# 2025-06-28.net
KiCad netlist of a schematic drawn in EasyEDA Pro
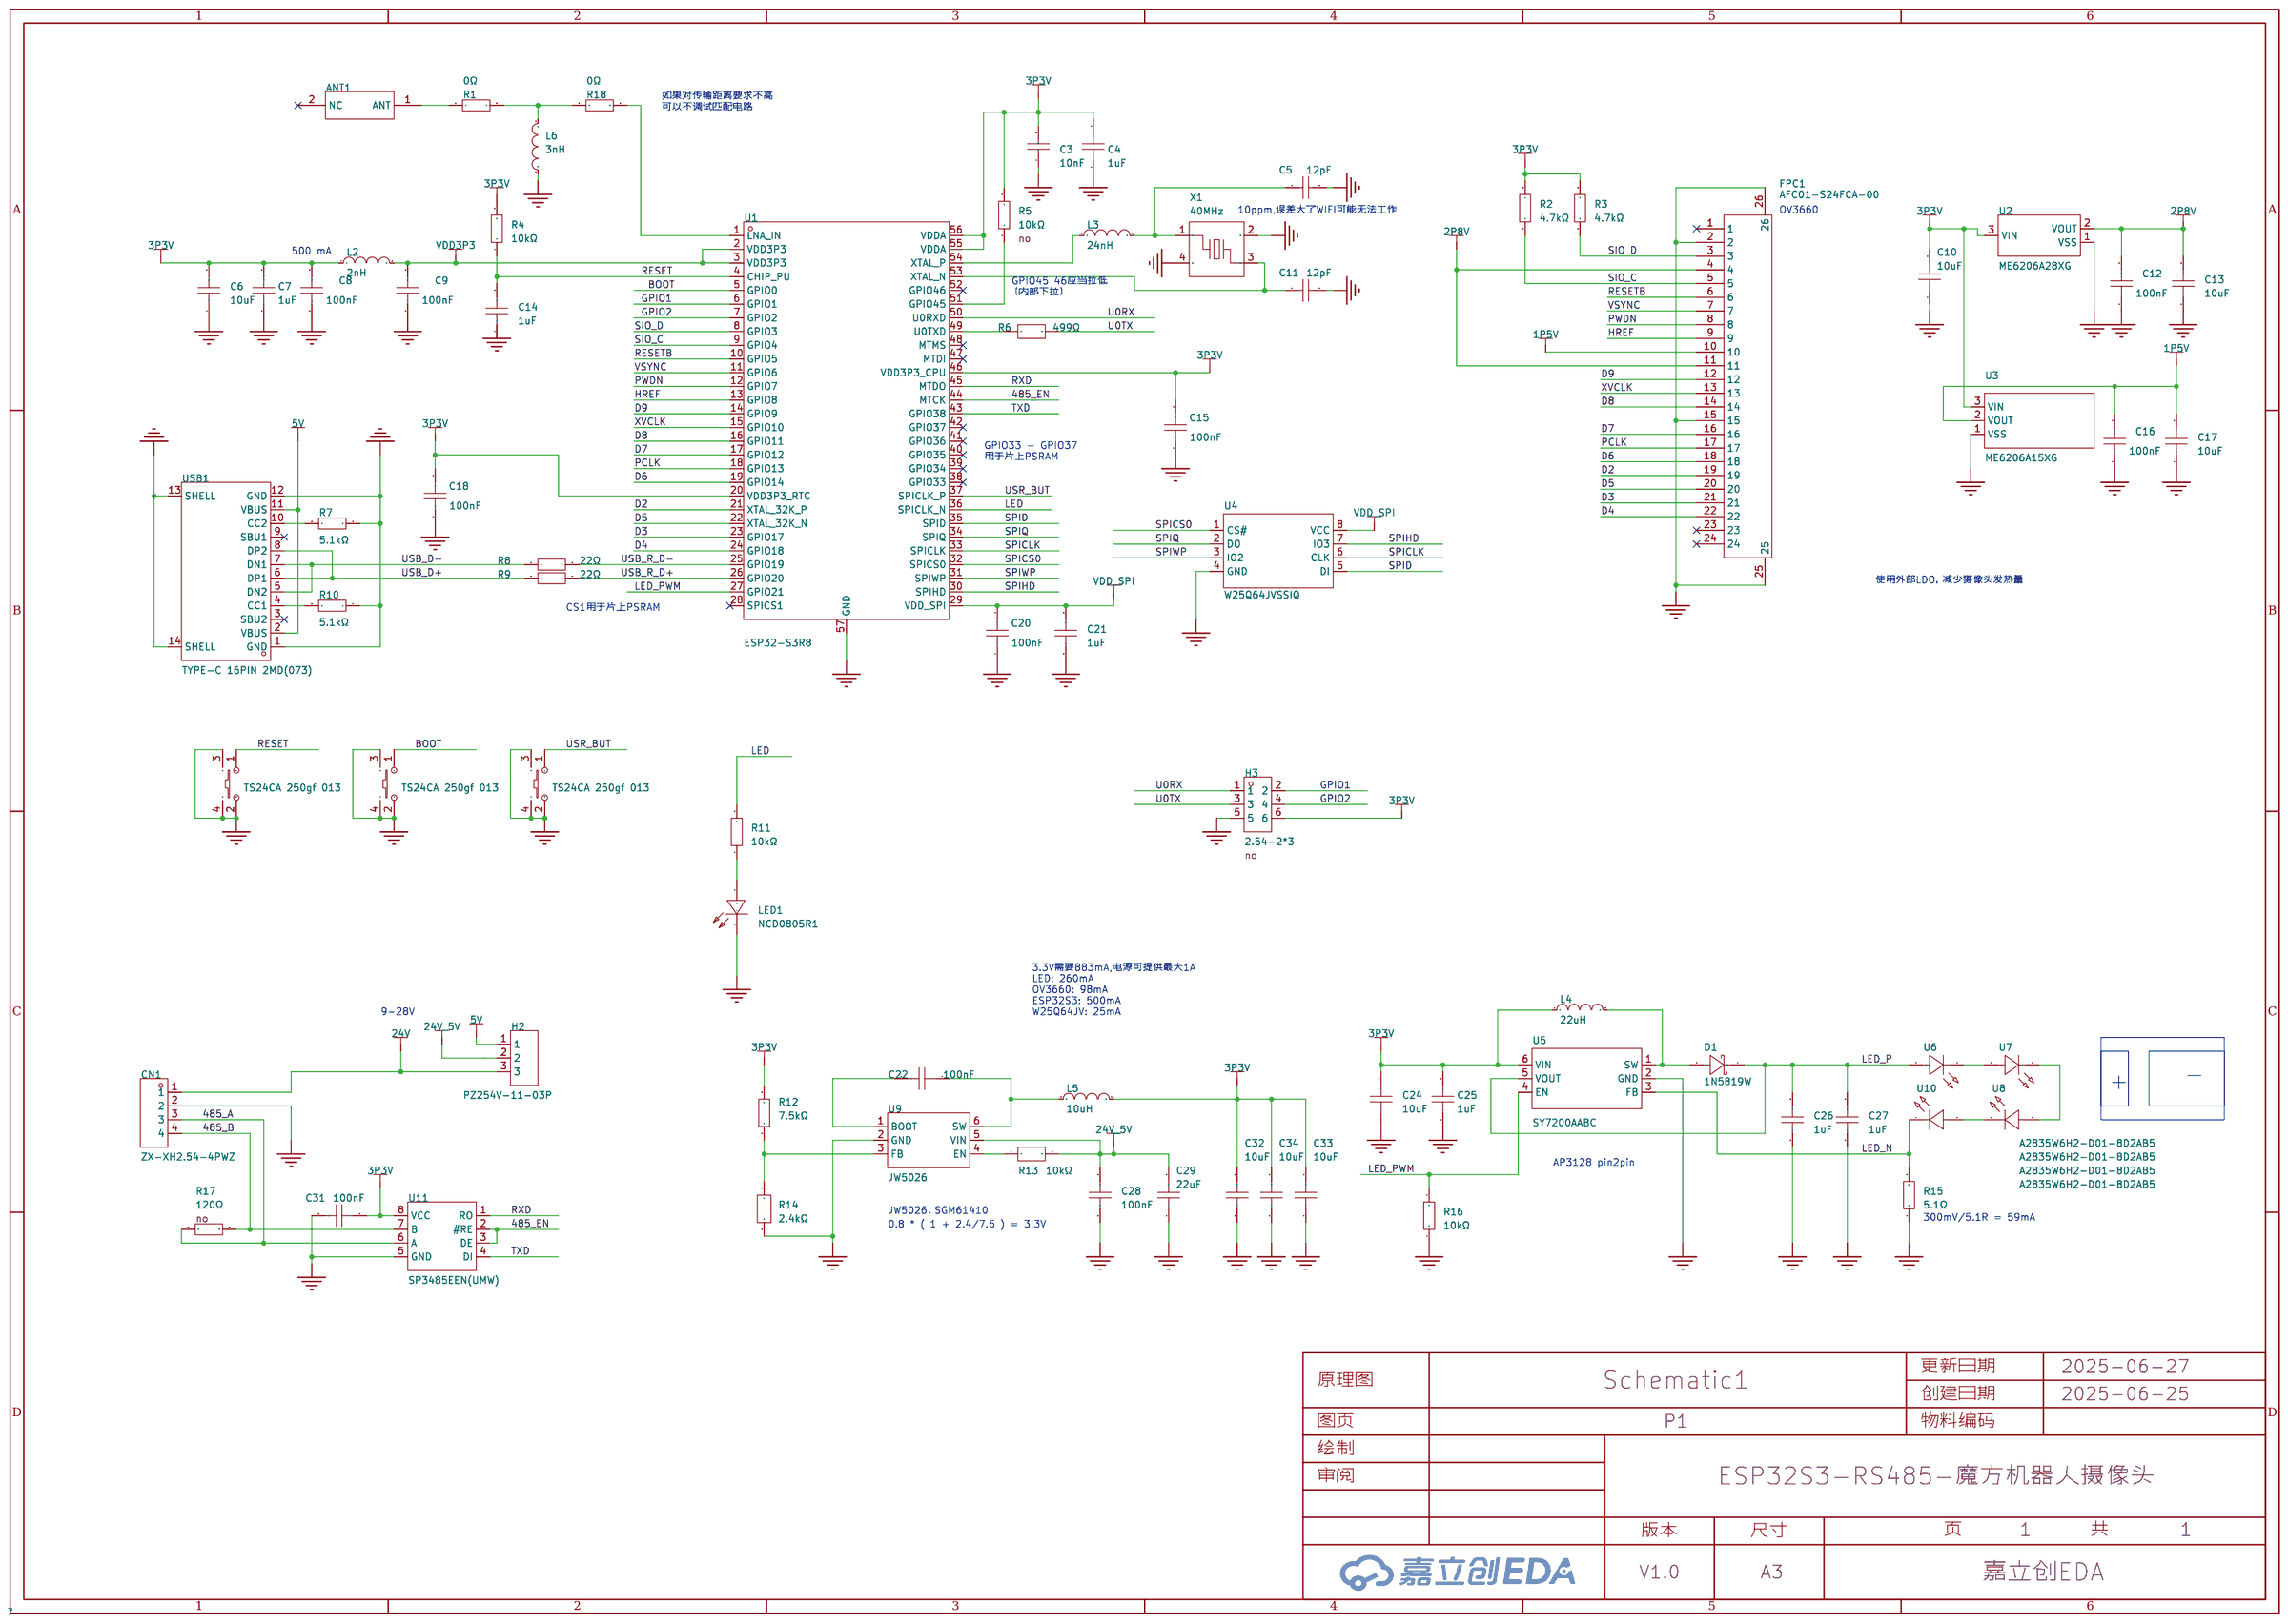
[diagram p0: schematic sheet]

(export (version "E")
  (design (tool "Eeschema 10.0.6"))
  (components
    (comp (ref "ANT1")
      (value "~")
      (footprint "easyedapro:CA-C03")
      (libsource (lib "easyedapro") (part "CA-C03"))
    )
    (comp (ref "C3")
      (value "10nF")
      (footprint "easyedapro:C0603")
      (description "容值:10nF;精度:±10%;额定电压:50V;温度系数:X7R;")
      (fields (field (name "Manufacturer Part") "0603B103K500NT") (field (name "Manufacturer") "FH(风华)"))
      (libsource (lib "easyedapro") (part "0603B103K500NT"))
    )
    (comp (ref "C4")
      (value "1uF")
      (footprint "easyedapro:C0603")
      (description "容值:1uF;精度:±10%;额定电压:50V;材质(温度系数):X5R;")
      (fields
        (field (name "Manufacturer Part") "CL10A105KB8NNNC")
        (field (name "Manufacturer") "SAMSUNG(三星)")
      )
      (libsource (lib "easyedapro") (part "CL10A105KB8NNNC"))
    )
    (comp (ref "C5")
      (value "12pF")
      (footprint "easyedapro:C0603")
      (description "容值:12pF;精度:±5%;额定电压:50V;材质(温度系数):C0G;")
      (fields
        (field (name "Manufacturer Part") "CL10C120JB8NNNC")
        (field (name "Manufacturer") "SAMSUNG(三星)")
      )
      (libsource (lib "easyedapro") (part "CL10C120JB8NNNC"))
    )
    (comp (ref "C6")
      (value "10uF")
      (footprint "easyedapro:C0603")
      (description "容值:10uF;精度:±10%;额定电压:10V;材质(温度系数):X5R;")
      (fields
        (field (name "Manufacturer Part") "CL10A106KP8NNNC")
        (field (name "Manufacturer") "SAMSUNG(三星)")
      )
      (libsource (lib "easyedapro") (part "CL10A106KP8NNNC"))
    )
    (comp (ref "C7")
      (value "1uF")
      (footprint "easyedapro:C0603")
      (description "容值:1uF;精度:±10%;额定电压:50V;材质(温度系数):X5R;")
      (fields
        (field (name "Manufacturer Part") "CL10A105KB8NNNC")
        (field (name "Manufacturer") "SAMSUNG(三星)")
      )
      (libsource (lib "easyedapro") (part "CL10A105KB8NNNC"))
    )
    (comp (ref "C8")
      (value "100nF")
      (footprint "easyedapro:C0603")
      (description "容值:100nF;精度:±10%;额定电压:50V;材质(温度系数):X7R;")
      (fields
        (field (name "Manufacturer Part") "CC0603KRX7R9BB104")
        (field (name "Manufacturer") "YAGEO(国巨)")
      )
      (libsource (lib "easyedapro") (part "CC0603KRX7R9BB104"))
    )
    (comp (ref "C9")
      (value "100nF")
      (footprint "easyedapro:C0603")
      (description "容值:100nF;精度:±10%;额定电压:50V;材质(温度系数):X7R;")
      (fields
        (field (name "Manufacturer Part") "CC0603KRX7R9BB104")
        (field (name "Manufacturer") "YAGEO(国巨)")
      )
      (libsource (lib "easyedapro") (part "CC0603KRX7R9BB104"))
    )
    (comp (ref "C10")
      (value "10uF")
      (footprint "easyedapro:C0603")
      (description "容值:10uF;精度:±10%;额定电压:10V;材质(温度系数):X5R;")
      (fields
        (field (name "Manufacturer Part") "CL10A106KP8NNNC")
        (field (name "Manufacturer") "SAMSUNG(三星)")
      )
      (libsource (lib "easyedapro") (part "CL10A106KP8NNNC"))
    )
    (comp (ref "C11")
      (value "12pF")
      (footprint "easyedapro:C0603")
      (description "容值:12pF;精度:±5%;额定电压:50V;材质(温度系数):C0G;")
      (fields
        (field (name "Manufacturer Part") "CL10C120JB8NNNC")
        (field (name "Manufacturer") "SAMSUNG(三星)")
      )
      (libsource (lib "easyedapro") (part "CL10C120JB8NNNC"))
    )
    (comp (ref "C12")
      (value "100nF")
      (footprint "easyedapro:C0603")
      (description "容值:100nF;精度:±10%;额定电压:50V;材质(温度系数):X7R;")
      (fields
        (field (name "Manufacturer Part") "CC0603KRX7R9BB104")
        (field (name "Manufacturer") "YAGEO(国巨)")
      )
      (libsource (lib "easyedapro") (part "CC0603KRX7R9BB104"))
    )
    (comp (ref "C13")
      (value "10uF")
      (footprint "easyedapro:C0603")
      (description "容值:10uF;精度:±10%;额定电压:10V;材质(温度系数):X5R;")
      (fields
        (field (name "Manufacturer Part") "CL10A106KP8NNNC")
        (field (name "Manufacturer") "SAMSUNG(三星)")
      )
      (libsource (lib "easyedapro") (part "CL10A106KP8NNNC"))
    )
    (comp (ref "C14")
      (value "1uF")
      (footprint "easyedapro:C0603")
      (description "容值:1uF;精度:±10%;额定电压:50V;材质(温度系数):X5R;")
      (fields
        (field (name "Manufacturer Part") "CL10A105KB8NNNC")
        (field (name "Manufacturer") "SAMSUNG(三星)")
      )
      (libsource (lib "easyedapro") (part "CL10A105KB8NNNC"))
    )
    (comp (ref "C15")
      (value "100nF")
      (footprint "easyedapro:C0603")
      (description "容值:100nF;精度:±10%;额定电压:50V;材质(温度系数):X7R;")
      (fields
        (field (name "Manufacturer Part") "CC0603KRX7R9BB104")
        (field (name "Manufacturer") "YAGEO(国巨)")
      )
      (libsource (lib "easyedapro") (part "CC0603KRX7R9BB104"))
    )
    (comp (ref "C16")
      (value "100nF")
      (footprint "easyedapro:C0603")
      (description "容值:100nF;精度:±10%;额定电压:50V;材质(温度系数):X7R;")
      (fields
        (field (name "Manufacturer Part") "CC0603KRX7R9BB104")
        (field (name "Manufacturer") "YAGEO(国巨)")
      )
      (libsource (lib "easyedapro") (part "CC0603KRX7R9BB104"))
    )
    (comp (ref "C17")
      (value "10uF")
      (footprint "easyedapro:C0603")
      (description "容值:10uF;精度:±10%;额定电压:10V;材质(温度系数):X5R;")
      (fields
        (field (name "Manufacturer Part") "CL10A106KP8NNNC")
        (field (name "Manufacturer") "SAMSUNG(三星)")
      )
      (libsource (lib "easyedapro") (part "CL10A106KP8NNNC"))
    )
    (comp (ref "C18")
      (value "100nF")
      (footprint "easyedapro:C0603")
      (description "容值:100nF;精度:±10%;额定电压:50V;材质(温度系数):X7R;")
      (fields
        (field (name "Manufacturer Part") "CC0603KRX7R9BB104")
        (field (name "Manufacturer") "YAGEO(国巨)")
      )
      (libsource (lib "easyedapro") (part "CC0603KRX7R9BB104"))
    )
    (comp (ref "C20")
      (value "100nF")
      (footprint "easyedapro:C0603")
      (description "容值:100nF;精度:±10%;额定电压:50V;材质(温度系数):X7R;")
      (fields
        (field (name "Manufacturer Part") "CC0603KRX7R9BB104")
        (field (name "Manufacturer") "YAGEO(国巨)")
      )
      (libsource (lib "easyedapro") (part "CC0603KRX7R9BB104"))
    )
    (comp (ref "C21")
      (value "1uF")
      (footprint "easyedapro:C0603")
      (description "容值:1uF;精度:±10%;额定电压:50V;材质(温度系数):X5R;")
      (fields
        (field (name "Manufacturer Part") "CL10A105KB8NNNC")
        (field (name "Manufacturer") "SAMSUNG(三星)")
      )
      (libsource (lib "easyedapro") (part "CL10A105KB8NNNC"))
    )
    (comp (ref "C22")
      (value "100nF")
      (footprint "easyedapro:C0603")
      (description "容值:100nF;精度:±10%;额定电压:50V;材质(温度系数):X7R;")
      (fields
        (field (name "Manufacturer Part") "CC0603KRX7R9BB104")
        (field (name "Manufacturer") "YAGEO(国巨)")
      )
      (libsource (lib "easyedapro") (part "CC0603KRX7R9BB104"))
    )
    (comp (ref "C24")
      (value "10uF")
      (footprint "easyedapro:C0603")
      (description "容值:10uF;精度:±10%;额定电压:10V;材质(温度系数):X5R;")
      (fields
        (field (name "Manufacturer Part") "CL10A106KP8NNNC")
        (field (name "Manufacturer") "SAMSUNG(三星)")
      )
      (libsource (lib "easyedapro") (part "CL10A106KP8NNNC"))
    )
    (comp (ref "C25")
      (value "1uF")
      (footprint "easyedapro:C0603")
      (description "容值:1uF;精度:±10%;额定电压:50V;材质(温度系数):X5R;")
      (fields
        (field (name "Manufacturer Part") "CL10A105KB8NNNC")
        (field (name "Manufacturer") "SAMSUNG(三星)")
      )
      (libsource (lib "easyedapro") (part "CL10A105KB8NNNC"))
    )
    (comp (ref "C26")
      (value "1uF")
      (footprint "easyedapro:C0603")
      (description "容值:1uF;精度:±10%;额定电压:50V;材质(温度系数):X5R;")
      (fields
        (field (name "Manufacturer Part") "CL10A105KB8NNNC")
        (field (name "Manufacturer") "SAMSUNG(三星)")
      )
      (libsource (lib "easyedapro") (part "CL10A105KB8NNNC"))
    )
    (comp (ref "C27")
      (value "1uF")
      (footprint "easyedapro:C0603")
      (description "容值:1uF;精度:±10%;额定电压:50V;材质(温度系数):X5R;")
      (fields
        (field (name "Manufacturer Part") "CL10A105KB8NNNC")
        (field (name "Manufacturer") "SAMSUNG(三星)")
      )
      (libsource (lib "easyedapro") (part "CL10A105KB8NNNC"))
    )
    (comp (ref "C28")
      (value "100nF")
      (footprint "easyedapro:C0603")
      (description "容值:100nF;精度:±10%;额定电压:50V;材质(温度系数):X7R;")
      (fields
        (field (name "Manufacturer Part") "CC0603KRX7R9BB104")
        (field (name "Manufacturer") "YAGEO(国巨)")
      )
      (libsource (lib "easyedapro") (part "CC0603KRX7R9BB104"))
    )
    (comp (ref "C29")
      (value "22uF")
      (footprint "easyedapro:C0805")
      (description "容值:22uF;精度:±20%;额定电压:35V;材质(温度系数):X5R;")
      (fields
        (field (name "Manufacturer Part") "CGA0805X5R226M350MT")
        (field (name "Manufacturer") "HRE(芯声)")
      )
      (libsource (lib "easyedapro") (part "CGA0805X5R226M350MT"))
    )
    (comp (ref "C31")
      (value "100nF")
      (footprint "easyedapro:C0603")
      (description "容值:100nF;精度:±10%;额定电压:50V;材质(温度系数):X7R;")
      (fields
        (field (name "Manufacturer Part") "CC0603KRX7R9BB104")
        (field (name "Manufacturer") "YAGEO(国巨)")
      )
      (libsource (lib "easyedapro") (part "CC0603KRX7R9BB104"))
    )
    (comp (ref "C32")
      (value "10uF")
      (footprint "easyedapro:C0603")
      (description "容值:10uF;精度:±10%;额定电压:10V;材质(温度系数):X5R;")
      (fields
        (field (name "Manufacturer Part") "CL10A106KP8NNNC")
        (field (name "Manufacturer") "SAMSUNG(三星)")
      )
      (libsource (lib "easyedapro") (part "CL10A106KP8NNNC"))
    )
    (comp (ref "C33")
      (value "10uF")
      (footprint "easyedapro:C0603")
      (description "容值:10uF;精度:±10%;额定电压:10V;材质(温度系数):X5R;")
      (fields
        (field (name "Manufacturer Part") "CL10A106KP8NNNC")
        (field (name "Manufacturer") "SAMSUNG(三星)")
      )
      (libsource (lib "easyedapro") (part "CL10A106KP8NNNC"))
    )
    (comp (ref "C34")
      (value "10uF")
      (footprint "easyedapro:C0603")
      (description "容值:10uF;精度:±10%;额定电压:10V;材质(温度系数):X5R;")
      (fields
        (field (name "Manufacturer Part") "CL10A106KP8NNNC")
        (field (name "Manufacturer") "SAMSUNG(三星)")
      )
      (libsource (lib "easyedapro") (part "CL10A106KP8NNNC"))
    )
    (comp (ref "CN1")
      (value "ZX-XH2.54-4PWZ")
      (footprint "easyedapro:CONN-TH_4P-P2.50_ZX-XH2.54-4PWZ")
      (fields (field (name "Manufacturer") "Megastar(兆星)"))
      (libsource (lib "easyedapro") (part "ZX-XH2.54-4PWZ"))
    )
    (comp (ref "D1")
      (value "1N5819W")
      (footprint "easyedapro:SOD-123_L2.7-W1.6-LS3.7-RD")
      (description "二极管配置:独立式;正向压降(Vf):600mV@200mA;直流反向耐压(Vr):40V;整流电流:350mA;")
      (fields (field (name "Manufacturer") "JSMSEMI(杰盛微)"))
      (libsource (lib "easyedapro") (part "1N5819W_C963381"))
    )
    (comp (ref "FPC1")
      (value "AFC01-S24FCA-00")
      (footprint "easyedapro:FPC-SMD_24P-P0.50_AFC01-S24FCA-00")
      (description "锁定特性:翻盖式;触点类型:下接;触点数量:24P;间距:0.5mm;安装类型:卧贴;")
      (fields (field (name "Manufacturer") "JS(钜硕电子)"))
      (libsource (lib "easyedapro") (part "AFC01-S24FCA-00"))
    )
    (comp (ref "H2")
      (value "PZ254V-11-03P")
      (footprint "easyedapro:HDR-TH_3P-P2.54-V-M")
      (fields (field (name "Manufacturer") "XFCN(兴飞)"))
      (libsource (lib "easyedapro") (part "PZ254V-11-03P_C2937625"))
    )
    (comp (ref "H3")
      (value "2.54-2*3")
      (footprint "easyedapro:HDR-TH_6P-P2.54-V-R2-C3-S2.54_A2541WV-2X3P")
      (description "插针结构:2x3P;间距:2.54mm;排数:双排;总PIN位数:6P;")
      (fields (field (name "Manufacturer") "ZHOURI(洲日)") (field (name "Add into BOM") "no"))
      (libsource (lib "easyedapro") (part "2.54-2*3"))
    )
    (comp (ref "L2")
      (value "2nH")
      (footprint "easyedapro:L0603")
      (description "电感值:2nH;额定电流:-;饱和电流(Isat):-;直流电阻(DCR):-;")
      (fields
        (field (name "Manufacturer Part") "SDCL1608C2N0STDF")
        (field (name "Manufacturer") "Sunlord(顺络)")
      )
      (libsource (lib "easyedapro") (part "SDCL1608C2N0STDF_C370234"))
    )
    (comp (ref "L3")
      (value "24nH")
      (footprint "easyedapro:IND-SMD_L1.6-W0.8")
      (description "电感值:24nH;精度:±2%;额定电流:500mA;饱和电流(Isat):-;")
      (fields (field (name "Manufacturer Part") "LQW18AN24NG00D") (field (name "Manufacturer") "muRata(村田)"))
      (libsource (lib "easyedapro") (part "LQW18AN24NG00D"))
    )
    (comp (ref "L4")
      (value "22uH")
      (footprint "easyedapro:IND-SMD_L4.0-W4.0")
      (description "电感值:22uH;精度:±20%;额定电流:1.1A;饱和电流(Isat):1.5A;")
      (fields
        (field (name "Manufacturer Part") "FHD4020S-220MT")
        (field (name "Manufacturer") "cjiang(长江微电)")
      )
      (libsource (lib "easyedapro") (part "FHD4020S-220MT"))
    )
    (comp (ref "L5")
      (value "10uH")
      (footprint "easyedapro:IND-SMD_L4.0-W4.0")
      (description "电感值:22uH;精度:±20%;额定电流:1.1A;饱和电流(Isat):1.5A;")
      (fields (field (name "Manufacturer Part") "FNR4030S100MT") (field (name "Manufacturer") "cjiang(长江微电)"))
      (libsource (lib "easyedapro") (part "FHD4020S-220MT"))
    )
    (comp (ref "L6")
      (value "3nH")
      (footprint "easyedapro:L0402")
      (description "电感值:3nH;精度:-;额定电流:800mA;饱和电流(Isat):-;直流电阻(DCR):125mΩ;")
      (fields (field (name "Manufacturer Part") "LQG15HS3N0S02D") (field (name "Manufacturer") "muRata(村田)"))
      (libsource (lib "easyedapro") (part "LQG15HS3N0S02D"))
    )
    (comp (ref "LED1")
      (value "NCD0805R1")
      (footprint "easyedapro:LED0805-R-RD")
      (fields (field (name "Manufacturer") "国星光电"))
      (libsource (lib "easyedapro") (part "FC-2012HRK-620D"))
    )
    (comp (ref "R1")
      (value "0Ω")
      (footprint "easyedapro:R0402")
      (description "电阻类型:厚膜电阻;阻值:0Ω;精度:±1%;功率:62.5mW;最大工作电压:50V;温度系数:±800ppm/°C;")
      (fields
        (field (name "Manufacturer Part") "0402WGF0000TCE")
        (field (name "Manufacturer") "UNI-ROYAL(厚声)")
      )
      (libsource (lib "easyedapro") (part "0402WGF0000TCE"))
    )
    (comp (ref "R2")
      (value "4.7kΩ")
      (footprint "easyedapro:R0603")
      (description "电阻类型:厚膜电阻;阻值:4.7kΩ;精度:±1%;功率:100mW;最大工作电压:75V;温度系数:±100ppm/°C;")
      (fields
        (field (name "Manufacturer Part") "0603WAF4701T5E")
        (field (name "Manufacturer") "UNI-ROYAL(厚声)")
      )
      (libsource (lib "easyedapro") (part "0603WAF4701T5E"))
    )
    (comp (ref "R3")
      (value "4.7kΩ")
      (footprint "easyedapro:R0603")
      (description "电阻类型:厚膜电阻;阻值:4.7kΩ;精度:±1%;功率:100mW;最大工作电压:75V;温度系数:±100ppm/°C;")
      (fields
        (field (name "Manufacturer Part") "0603WAF4701T5E")
        (field (name "Manufacturer") "UNI-ROYAL(厚声)")
      )
      (libsource (lib "easyedapro") (part "0603WAF4701T5E"))
    )
    (comp (ref "R4")
      (value "10kΩ")
      (footprint "easyedapro:R0603")
      (description "电阻类型:厚膜电阻;阻值:10kΩ;精度:±1%;功率:100mW;工作电压:75V;温度系数:±100ppm/°C;")
      (fields
        (field (name "Manufacturer Part") "0603WAF1002T5E")
        (field (name "Manufacturer") "UNI-ROYAL(厚声)")
      )
      (libsource (lib "easyedapro") (part "0603WAF1002T5E"))
    )
    (comp (ref "R5")
      (value "10kΩ")
      (footprint "easyedapro:R0603")
      (description "电阻类型:厚膜电阻;阻值:10kΩ;精度:±1%;功率:100mW;工作电压:75V;温度系数:±100ppm/°C;")
      (fields
        (field (name "Manufacturer Part") "0603WAF1002T5E")
        (field (name "Manufacturer") "UNI-ROYAL(厚声)")
        (field (name "Add into BOM") "no")
      )
      (libsource (lib "easyedapro") (part "0603WAF1002T5E"))
    )
    (comp (ref "R6")
      (value "499Ω")
      (footprint "easyedapro:R0603")
      (description "电阻类型:厚膜电阻;阻值:499Ω;精度:±1%;功率:100mW;工作电压:75V;温度系数:±100ppm/°C;")
      (fields (field (name "Manufacturer Part") "FRC0603F4990TS") (field (name "Manufacturer") "FOJAN(富捷)"))
      (libsource (lib "easyedapro") (part "FRC0603F4990TS"))
    )
    (comp (ref "R7")
      (value "5.1kΩ")
      (footprint "easyedapro:R0603")
      (description "阻值:5.1kΩ;精度:±1%;功率:100mW;温度系数:±100ppm/°C;电阻类型:厚膜电阻;")
      (fields
        (field (name "Manufacturer Part") "0603WAF5101T5E")
        (field (name "Manufacturer") "UNI-ROYAL(厚声)")
      )
      (libsource (lib "easyedapro") (part "0603WAF5101T5E"))
    )
    (comp (ref "R8")
      (value "22Ω")
      (footprint "easyedapro:R0603")
      (description "电阻类型:厚膜电阻;阻值:0Ω;精度:±1%;功率:100mW;最大工作电压:75V;")
      (fields
        (field (name "Manufacturer Part") "0603WAF220JT5E")
        (field (name "Manufacturer") "UNI-ROYAL(厚声)")
      )
      (libsource (lib "easyedapro") (part "0603WAF0000T5E"))
    )
    (comp (ref "R9")
      (value "22Ω")
      (footprint "easyedapro:R0603")
      (description "电阻类型:厚膜电阻;阻值:0Ω;精度:±1%;功率:100mW;最大工作电压:75V;")
      (fields
        (field (name "Manufacturer Part") "0603WAF220JT5E")
        (field (name "Manufacturer") "UNI-ROYAL(厚声)")
      )
      (libsource (lib "easyedapro") (part "0603WAF0000T5E"))
    )
    (comp (ref "R10")
      (value "5.1kΩ")
      (footprint "easyedapro:R0603")
      (description "阻值:5.1kΩ;精度:±1%;功率:100mW;温度系数:±100ppm/°C;电阻类型:厚膜电阻;")
      (fields
        (field (name "Manufacturer Part") "0603WAF5101T5E")
        (field (name "Manufacturer") "UNI-ROYAL(厚声)")
      )
      (libsource (lib "easyedapro") (part "0603WAF5101T5E"))
    )
    (comp (ref "R11")
      (value "10kΩ")
      (footprint "easyedapro:R0603")
      (description "电阻类型:厚膜电阻;阻值:10kΩ;精度:±1%;功率:100mW;工作电压:75V;温度系数:±100ppm/°C;")
      (fields
        (field (name "Manufacturer Part") "0603WAF1002T5E")
        (field (name "Manufacturer") "UNI-ROYAL(厚声)")
      )
      (libsource (lib "easyedapro") (part "0603WAF1002T5E"))
    )
    (comp (ref "R12")
      (value "7.5kΩ")
      (fields
        (field (name "Manufacturer Part") "0603WAF7501T5E")
        (field (name "Manufacturer") "UNI-ROYAL(厚声)")
      )
      (libsource (lib "easyedapro") (part "0603waf4702t5e"))
    )
    (comp (ref "R13")
      (value "10kΩ")
      (footprint "easyedapro:R0603")
      (description "电阻类型:薄膜电阻;阻值:10kΩ;精度:±0.1%;功率:100mW;")
      (fields (field (name "Manufacturer Part") "AT0603BRD0710KL") (field (name "Manufacturer") "YAGEO(国巨)"))
      (libsource (lib "easyedapro") (part "AT0603BRD0710KL"))
    )
    (comp (ref "R14")
      (value "2.4kΩ")
      (fields (field (name "Manufacturer Part") "FRC0603F2401TS") (field (name "Manufacturer") "FOJAN(富捷)"))
      (libsource (lib "easyedapro") (part "FRC0603F1502TS"))
    )
    (comp (ref "R15")
      (value "5.1Ω")
      (footprint "easyedapro:R0603")
      (description "电阻类型:厚膜电阻;阻值:5.1Ω;精度:±1%;功率:100mW;最大工作电压:75V;温度系数:±200ppm/°C;")
      (fields
        (field (name "Manufacturer Part") "0603WAF510KT5E")
        (field (name "Manufacturer") "UNI-ROYAL(厚声)")
      )
      (libsource (lib "easyedapro") (part "0603WAF510KT5E"))
    )
    (comp (ref "R16")
      (value "10kΩ")
      (footprint "easyedapro:R0603")
      (description "电阻类型:厚膜电阻;阻值:10kΩ;精度:±1%;功率:100mW;工作电压:75V;温度系数:±100ppm/°C;")
      (fields
        (field (name "Manufacturer Part") "0603WAF1002T5E")
        (field (name "Manufacturer") "UNI-ROYAL(厚声)")
      )
      (libsource (lib "easyedapro") (part "0603WAF1002T5E"))
    )
    (comp (ref "R17")
      (value "120Ω")
      (footprint "easyedapro:R0603")
      (description "电阻类型:厚膜电阻;阻值:120Ω;精度:±1%;功率:100mW;最大工作电压:75V;温度系数:±100ppm/°C;")
      (fields
        (field (name "Manufacturer Part") "0603WAF1200T5E")
        (field (name "Manufacturer") "UNI-ROYAL(厚声)")
        (field (name "Add into BOM") "no")
      )
      (libsource (lib "easyedapro") (part "0603WAF1200T5E"))
    )
    (comp (ref "R18")
      (value "0Ω")
      (footprint "easyedapro:R0402")
      (description "电阻类型:厚膜电阻;阻值:0Ω;精度:±1%;功率:62.5mW;最大工作电压:50V;温度系数:±800ppm/°C;")
      (fields
        (field (name "Manufacturer Part") "0402WGF0000TCE")
        (field (name "Manufacturer") "UNI-ROYAL(厚声)")
      )
      (libsource (lib "easyedapro") (part "0402WGF0000TCE"))
    )
    (comp (ref "SW1")
      (value "TS24CA 250gf 013")
      (footprint "easyedapro:SW-SMD_L4.7-W3.5-P3.35-EH")
      (fields (field (name "Manufacturer") "SHOU HAN(首韩)"))
      (libsource (lib "easyedapro") (part "TS24CA 250GF 013"))
    )
    (comp (ref "SW2")
      (value "TS24CA 250gf 013")
      (footprint "easyedapro:SW-SMD_L4.7-W3.5-P3.35-EH")
      (fields (field (name "Manufacturer") "SHOU HAN(首韩)"))
      (libsource (lib "easyedapro") (part "TS24CA 250GF 013"))
    )
    (comp (ref "SW3")
      (value "TS24CA 250gf 013")
      (footprint "easyedapro:SW-SMD_L4.7-W3.5-P3.35-EH")
      (fields (field (name "Manufacturer") "SHOU HAN(首韩)"))
      (libsource (lib "easyedapro") (part "TS24CA 250GF 013"))
    )
    (comp (ref "U1")
      (value "ESP32-S3R8")
      (footprint "easyedapro:QFN-56_L7.0-W7.0-P0.40-TL-EP4.0")
      (fields (field (name "Manufacturer") "ESPRESSIF(乐鑫)"))
      (libsource (lib "easyedapro") (part "ESP32-S3(R8)"))
    )
    (comp (ref "U2")
      (value "ME6206A28XG")
      (footprint "easyedapro:SOT-23_L2.9-W1.3-P1.90-LS2.4-BR")
      (description "输出类型:固定;工作电压:6V;输出电压:2.8V;输出电流:300mA;电源纹波抑制比(PSRR):50dB@(1kHz);输出极性:正极;")
      (fields (field (name "Manufacturer") "MICRONE(南京微盟)"))
      (libsource (lib "easyedapro") (part "ME6206A28XG"))
    )
    (comp (ref "U3")
      (value "ME6206A15XG")
      (footprint "easyedapro:SOT-23-3_L2.9-W1.6-P1.90-LS2.8-BR")
      (description "输出类型:固定;工作电压:6V;输出电压:1.5V;输出电流:100mA;电源纹波抑制比(PSRR):45dB@(1kHz);输出极性:正极;")
      (fields (field (name "Manufacturer") "MICRONE(南京微盟)"))
      (libsource (lib "easyedapro") (part "ME6206A15XG"))
    )
    (comp (ref "U4")
      (value "W25Q64JVSSIQ")
      (footprint "easyedapro:SOP-8_L5.3-W5.3-P1.27-LS8.0-BL")
      (description "接口类型:SPI;存储容量:-;时钟频率(fc):133MHz;")
      (fields (field (name "Manufacturer") "WINBOND(华邦)"))
      (libsource (lib "easyedapro") (part "W25Q64JVSSIQ"))
    )
    (comp (ref "U5")
      (value "SY7200AABC")
      (footprint "easyedapro:SOT-23-6_L2.9-W1.6-P0.95-LS2.8-BR")
      (description "类型:-;工作电压:2.5V~5.5V;开关频率:-;通道数:-;输出电压:-;调光:-;拓扑结构:升压;")
      (fields (field (name "Manufacturer") "silergy(矽力杰)"))
      (libsource (lib "easyedapro") (part "AP3128AE3036ES6"))
    )
    (comp (ref "U6")
      (value "A2835W6H2-D01-8D2AB5")
      (footprint "easyedapro:LED-SMD_L3.5-W2.8-FD-2835_WHITE")
      (description "发光颜色:白色;正向电压(VF):2.9V~3.3V;正向电流:-;色温:6500K;")
      (fields (field (name "Manufacturer") "HONGLITRONIC(鸿利光电)"))
      (libsource (lib "easyedapro") (part "A2835W6H2-D01-8D2AB5"))
    )
    (comp (ref "U7")
      (value "A2835W6H2-D01-8D2AB5")
      (footprint "easyedapro:LED-SMD_L3.5-W2.8-FD-2835_WHITE")
      (description "发光颜色:白色;正向电压(VF):2.9V~3.3V;正向电流:-;色温:6500K;")
      (fields (field (name "Manufacturer") "HONGLITRONIC(鸿利光电)"))
      (libsource (lib "easyedapro") (part "A2835W6H2-D01-8D2AB5"))
    )
    (comp (ref "U8")
      (value "A2835W6H2-D01-8D2AB5")
      (footprint "easyedapro:LED-SMD_L3.5-W2.8-FD-2835_WHITE")
      (description "发光颜色:白色;正向电压(VF):2.9V~3.3V;正向电流:-;色温:6500K;")
      (fields (field (name "Manufacturer") "HONGLITRONIC(鸿利光电)"))
      (libsource (lib "easyedapro") (part "A2835W6H2-D01-8D2AB5"))
    )
    (comp (ref "U9")
      (value "JW5026")
      (footprint "easyedapro:TSOT-23-6_L2.9-W1.6-P0.95-LS2.8-BL")
      (fields (field (name "Manufacturer") "Joulwatt(杰华特)"))
      (libsource (lib "easyedapro") (part "SGM61410XN6G/TR"))
    )
    (comp (ref "U10")
      (value "A2835W6H2-D01-8D2AB5")
      (footprint "easyedapro:LED-SMD_L3.5-W2.8-FD-2835_WHITE")
      (description "发光颜色:白色;正向电压(VF):2.9V~3.3V;正向电流:-;色温:6500K;")
      (fields (field (name "Manufacturer") "HONGLITRONIC(鸿利光电)"))
      (libsource (lib "easyedapro") (part "A2835W6H2-D01-8D2AB5"))
    )
    (comp (ref "U11")
      (value "SP3485EEN(UMW)")
      (footprint "easyedapro:SOP-8_L5.0-W4.0-P1.27-LS6.0-BL")
      (description "类型:收发器;数据速率:12Mbps;")
      (fields (field (name "Manufacturer") "UMW(友台半导体)"))
      (libsource (lib "easyedapro") (part "SP3485EEN"))
    )
    (comp (ref "USB1")
      (value "TYPE-C 16PIN 2MD(073)")
      (footprint "easyedapro:USB-C-SMD_TYPE-C-6PIN-2MD-073")
      (description "连接器类型:Type-C;标准:-;公母:母;触点数量:16P;端口数量:1;安装方式:卧贴;额定电流 - 电源:5A;工作温度范围:-25°C~+85°C;")
      (fields (field (name "Manufacturer") "SHOU HAN(首韩)"))
      (libsource (lib "easyedapro") (part "TYPE-C 16PIN 2MD(073)"))
    )
    (comp (ref "X1")
      (value "40MHz")
      (footprint "easyedapro:CRYSTAL-SMD_4P-L3.2-W2.5-BL_SIT8008BI")
      (description "晶振类型:贴片晶振;频率:40MHz;常温频差:±10ppm;负载电容:10pF;频率稳定度:±30ppm;")
      (fields (field (name "Manufacturer Part") "CF4040M00010001") (field (name "Manufacturer") "HUAXIN(华昕)"))
      (libsource (lib "easyedapro") (part "CF4040M00010001"))
    )
  )
  (nets
    (net (code "1") (name "/485_A") (class "Default")
      (node (ref "CN1") (pin "3") (pinfunction "3_3") (pintype "unspecified"))
      (node (ref "R17") (pin "1") (pinfunction "1_1") (pintype "input"))
      (node (ref "U11") (pin "6") (pinfunction "A_6") (pintype "unspecified"))
    )
    (net (code "2") (name "/485_B") (class "Default")
      (node (ref "CN1") (pin "4") (pinfunction "4_4") (pintype "unspecified"))
      (node (ref "R17") (pin "2") (pinfunction "2_2") (pintype "input"))
      (node (ref "U11") (pin "7") (pinfunction "B_7") (pintype "unspecified"))
    )
    (net (code "3") (name "/485_EN") (class "Default")
      (node (ref "U1") (pin "44") (pinfunction "MTCK_44") (pintype "unspecified"))
      (node (ref "U11") (pin "2") (pinfunction "#RE_2") (pintype "unspecified"))
      (node (ref "U11") (pin "3") (pinfunction "DE_3") (pintype "unspecified"))
    )
    (net (code "4") (name "/BOOT") (class "Default")
      (node (ref "SW2") (pin "1") (pinfunction "1_1") (pintype "unspecified"))
      (node (ref "U1") (pin "5") (pinfunction "GPIO0_5") (pintype "unspecified"))
    )
    (net (code "5") (name "/D2") (class "Default")
      (node (ref "FPC1") (pin "19") (pinfunction "19_19") (pintype "unspecified"))
      (node (ref "U1") (pin "21") (pinfunction "XTAL_32K_P_21") (pintype "unspecified"))
    )
    (net (code "6") (name "/D3") (class "Default")
      (node (ref "FPC1") (pin "21") (pinfunction "21_21") (pintype "unspecified"))
      (node (ref "U1") (pin "23") (pinfunction "GPIO17_23") (pintype "unspecified"))
    )
    (net (code "7") (name "/D4") (class "Default")
      (node (ref "FPC1") (pin "22") (pinfunction "22_22") (pintype "unspecified"))
      (node (ref "U1") (pin "24") (pinfunction "GPIO18_24") (pintype "unspecified"))
    )
    (net (code "8") (name "/D5") (class "Default")
      (node (ref "FPC1") (pin "20") (pinfunction "20_20") (pintype "unspecified"))
      (node (ref "U1") (pin "22") (pinfunction "XTAL_32K_N_22") (pintype "unspecified"))
    )
    (net (code "9") (name "/D6") (class "Default")
      (node (ref "FPC1") (pin "18") (pinfunction "18_18") (pintype "unspecified"))
      (node (ref "U1") (pin "19") (pinfunction "GPIO14_19") (pintype "unspecified"))
    )
    (net (code "10") (name "/D7") (class "Default")
      (node (ref "FPC1") (pin "16") (pinfunction "16_16") (pintype "unspecified"))
      (node (ref "U1") (pin "17") (pinfunction "GPIO12_17") (pintype "unspecified"))
    )
    (net (code "11") (name "/D8") (class "Default")
      (node (ref "FPC1") (pin "14") (pinfunction "14_14") (pintype "unspecified"))
      (node (ref "U1") (pin "16") (pinfunction "GPIO11_16") (pintype "unspecified"))
    )
    (net (code "12") (name "/D9") (class "Default")
      (node (ref "FPC1") (pin "12") (pinfunction "12_12") (pintype "unspecified"))
      (node (ref "U1") (pin "14") (pinfunction "GPIO9_14") (pintype "unspecified"))
    )
    (net (code "13") (name "/GPIO1") (class "Default")
      (node (ref "H3") (pin "2") (pinfunction "2_2") (pintype "unspecified"))
      (node (ref "U1") (pin "6") (pinfunction "GPIO1_6") (pintype "unspecified"))
    )
    (net (code "14") (name "/GPIO2") (class "Default")
      (node (ref "H3") (pin "4") (pinfunction "4_4") (pintype "unspecified"))
      (node (ref "U1") (pin "7") (pinfunction "GPIO2_7") (pintype "unspecified"))
    )
    (net (code "15") (name "/HREF") (class "Default")
      (node (ref "FPC1") (pin "9") (pinfunction "9_9") (pintype "unspecified"))
      (node (ref "U1") (pin "13") (pinfunction "GPIO8_13") (pintype "unspecified"))
    )
    (net (code "16") (name "/LED") (class "Default")
      (node (ref "R11") (pin "2") (pinfunction "2_2") (pintype "input"))
      (node (ref "U1") (pin "36") (pinfunction "SPICLK_N_36") (pintype "unspecified"))
    )
    (net (code "17") (name "/LED_N") (class "Default")
      (node (ref "R15") (pin "2") (pinfunction "2_2") (pintype "input"))
      (node (ref "U10") (pin "1") (pinfunction "K_1") (pintype "unspecified"))
      (node (ref "U5") (pin "3") (pinfunction "FB_3") (pintype "unspecified"))
    )
    (net (code "18") (name "/LED_P") (class "Default")
      (node (ref "C26") (pin "2") (pinfunction "2_2") (pintype "unspecified"))
      (node (ref "C27") (pin "2") (pinfunction "2_2") (pintype "unspecified"))
      (node (ref "D1") (pin "1") (pinfunction "C_1") (pintype "unspecified"))
      (node (ref "U5") (pin "5") (pinfunction "VOUT_5") (pintype "unspecified"))
      (node (ref "U6") (pin "2") (pinfunction "A_2") (pintype "unspecified"))
    )
    (net (code "19") (name "/LED_PWM") (class "Default")
      (node (ref "R16") (pin "2") (pinfunction "2_2") (pintype "input"))
      (node (ref "U1") (pin "27") (pinfunction "GPIO21_27") (pintype "unspecified"))
      (node (ref "U5") (pin "4") (pinfunction "EN_4") (pintype "unspecified"))
    )
    (net (code "20") (name "/PCLK") (class "Default")
      (node (ref "FPC1") (pin "17") (pinfunction "17_17") (pintype "unspecified"))
      (node (ref "U1") (pin "18") (pinfunction "GPIO13_18") (pintype "unspecified"))
    )
    (net (code "21") (name "/PWDN") (class "Default")
      (node (ref "FPC1") (pin "8") (pinfunction "8_8") (pintype "unspecified"))
      (node (ref "U1") (pin "12") (pinfunction "GPIO7_12") (pintype "unspecified"))
    )
    (net (code "22") (name "/RESET") (class "Default")
      (node (ref "C14") (pin "2") (pinfunction "2_2") (pintype "unspecified"))
      (node (ref "R4") (pin "1") (pinfunction "1_1") (pintype "input"))
      (node (ref "SW1") (pin "1") (pinfunction "1_1") (pintype "unspecified"))
      (node (ref "U1") (pin "4") (pinfunction "CHIP_PU_4") (pintype "unspecified"))
    )
    (net (code "23") (name "/RESETB") (class "Default")
      (node (ref "FPC1") (pin "6") (pinfunction "6_6") (pintype "unspecified"))
      (node (ref "U1") (pin "10") (pinfunction "GPIO5_10") (pintype "unspecified"))
    )
    (net (code "24") (name "/RXD") (class "Default")
      (node (ref "U1") (pin "45") (pinfunction "MTDO_45") (pintype "unspecified"))
      (node (ref "U11") (pin "1") (pinfunction "RO_1") (pintype "unspecified"))
    )
    (net (code "25") (name "/SIO_C") (class "Default")
      (node (ref "FPC1") (pin "5") (pinfunction "5_5") (pintype "unspecified"))
      (node (ref "R2") (pin "1") (pinfunction "1_1") (pintype "input"))
      (node (ref "U1") (pin "9") (pinfunction "GPIO4_9") (pintype "unspecified"))
    )
    (net (code "26") (name "/SIO_D") (class "Default")
      (node (ref "FPC1") (pin "3") (pinfunction "3_3") (pintype "unspecified"))
      (node (ref "R3") (pin "1") (pinfunction "1_1") (pintype "input"))
      (node (ref "U1") (pin "8") (pinfunction "GPIO3_8") (pintype "unspecified"))
    )
    (net (code "27") (name "/SPICLK") (class "Default")
      (node (ref "U1") (pin "33") (pinfunction "SPICLK_33") (pintype "unspecified"))
      (node (ref "U4") (pin "6") (pinfunction "CLK_6") (pintype "unspecified"))
    )
    (net (code "28") (name "/SPICS0") (class "Default")
      (node (ref "U1") (pin "32") (pinfunction "SPICS0_32") (pintype "unspecified"))
      (node (ref "U4") (pin "1") (pinfunction "CS#_1") (pintype "unspecified"))
    )
    (net (code "29") (name "/SPID") (class "Default")
      (node (ref "U1") (pin "35") (pinfunction "SPID_35") (pintype "unspecified"))
      (node (ref "U4") (pin "5") (pinfunction "DI_5") (pintype "unspecified"))
    )
    (net (code "30") (name "/SPIHD") (class "Default")
      (node (ref "U1") (pin "30") (pinfunction "SPIHD_30") (pintype "unspecified"))
      (node (ref "U4") (pin "7") (pinfunction "IO3_7") (pintype "unspecified"))
    )
    (net (code "31") (name "/SPIQ") (class "Default")
      (node (ref "U1") (pin "34") (pinfunction "SPIQ_34") (pintype "unspecified"))
      (node (ref "U4") (pin "2") (pinfunction "DO_2") (pintype "unspecified"))
    )
    (net (code "32") (name "/SPIWP") (class "Default")
      (node (ref "U1") (pin "31") (pinfunction "SPIWP_31") (pintype "unspecified"))
      (node (ref "U4") (pin "3") (pinfunction "IO2_3") (pintype "unspecified"))
    )
    (net (code "33") (name "/TXD") (class "Default")
      (node (ref "U1") (pin "43") (pinfunction "GPIO38_43") (pintype "unspecified"))
      (node (ref "U11") (pin "4") (pinfunction "DI_4") (pintype "unspecified"))
    )
    (net (code "34") (name "/U0RX") (class "Default")
      (node (ref "H3") (pin "1") (pinfunction "1_1") (pintype "unspecified"))
      (node (ref "U1") (pin "50") (pinfunction "U0RXD_50") (pintype "unspecified"))
    )
    (net (code "35") (name "/U0TX") (class "Default")
      (node (ref "H3") (pin "3") (pinfunction "3_3") (pintype "unspecified"))
      (node (ref "R6") (pin "2") (pinfunction "2_2") (pintype "unspecified"))
    )
    (net (code "36") (name "/USB_D+") (class "Default")
      (node (ref "R9") (pin "1") (pinfunction "1_1") (pintype "input"))
      (node (ref "USB1") (pin "6") (pinfunction "DP1_6") (pintype "unspecified"))
      (node (ref "USB1") (pin "8") (pinfunction "DP2_8") (pintype "unspecified"))
    )
    (net (code "37") (name "/USB_D-") (class "Default")
      (node (ref "R8") (pin "1") (pinfunction "1_1") (pintype "input"))
      (node (ref "USB1") (pin "5") (pinfunction "DN2_5") (pintype "unspecified"))
      (node (ref "USB1") (pin "7") (pinfunction "DN1_7") (pintype "unspecified"))
    )
    (net (code "38") (name "/USB_R_D+") (class "Default")
      (node (ref "R9") (pin "2") (pinfunction "2_2") (pintype "input"))
      (node (ref "U1") (pin "26") (pinfunction "GPIO20_26") (pintype "unspecified"))
    )
    (net (code "39") (name "/USB_R_D-") (class "Default")
      (node (ref "R8") (pin "2") (pinfunction "2_2") (pintype "input"))
      (node (ref "U1") (pin "25") (pinfunction "GPIO19_25") (pintype "unspecified"))
    )
    (net (code "40") (name "/USR_BUT") (class "Default")
      (node (ref "SW3") (pin "1") (pinfunction "1_1") (pintype "unspecified"))
      (node (ref "U1") (pin "37") (pinfunction "SPICLK_P_37") (pintype "unspecified"))
    )
    (net (code "41") (name "/VSYNC") (class "Default")
      (node (ref "FPC1") (pin "7") (pinfunction "7_7") (pintype "unspecified"))
      (node (ref "U1") (pin "11") (pinfunction "GPIO6_11") (pintype "unspecified"))
    )
    (net (code "42") (name "/XVCLK") (class "Default")
      (node (ref "FPC1") (pin "13") (pinfunction "13_13") (pintype "unspecified"))
      (node (ref "U1") (pin "15") (pinfunction "GPIO10_15") (pintype "unspecified"))
    )
    (net (code "43") (name "1P5V") (class "Default")
      (node (ref "C16") (pin "2") (pinfunction "2_2") (pintype "unspecified"))
      (node (ref "C17") (pin "2") (pinfunction "2_2") (pintype "unspecified"))
      (node (ref "FPC1") (pin "10") (pinfunction "10_10") (pintype "unspecified"))
      (node (ref "U3") (pin "2") (pinfunction "VOUT_2") (pintype "unspecified"))
    )
    (net (code "44") (name "2P8V") (class "Default")
      (node (ref "C12") (pin "2") (pinfunction "2_2") (pintype "unspecified"))
      (node (ref "C13") (pin "2") (pinfunction "2_2") (pintype "unspecified"))
      (node (ref "FPC1") (pin "11") (pinfunction "11_11") (pintype "unspecified"))
      (node (ref "FPC1") (pin "4") (pinfunction "4_4") (pintype "unspecified"))
      (node (ref "U2") (pin "2") (pinfunction "VOUT_2") (pintype "unspecified"))
    )
    (net (code "45") (name "3P3V") (class "Default")
      (node (ref "C10") (pin "2") (pinfunction "2_2") (pintype "unspecified"))
      (node (ref "C15") (pin "2") (pinfunction "2_2") (pintype "unspecified"))
      (node (ref "C18") (pin "2") (pinfunction "2_2") (pintype "unspecified"))
      (node (ref "C24") (pin "2") (pinfunction "2_2") (pintype "unspecified"))
      (node (ref "C25") (pin "2") (pinfunction "2_2") (pintype "unspecified"))
      (node (ref "C3") (pin "2") (pinfunction "2_2") (pintype "input"))
      (node (ref "C31") (pin "1") (pinfunction "1_1") (pintype "unspecified"))
      (node (ref "C32") (pin "2") (pinfunction "2_2") (pintype "unspecified"))
      (node (ref "C33") (pin "2") (pinfunction "2_2") (pintype "unspecified"))
      (node (ref "C34") (pin "2") (pinfunction "2_2") (pintype "unspecified"))
      (node (ref "C4") (pin "2") (pinfunction "2_2") (pintype "unspecified"))
      (node (ref "C6") (pin "2") (pinfunction "2_2") (pintype "unspecified"))
      (node (ref "C7") (pin "2") (pinfunction "2_2") (pintype "unspecified"))
      (node (ref "C8") (pin "2") (pinfunction "2_2") (pintype "unspecified"))
      (node (ref "H3") (pin "6") (pinfunction "6_6") (pintype "unspecified"))
      (node (ref "L2") (pin "1") (pinfunction "1_1") (pintype "unspecified"))
      (node (ref "L4") (pin "1") (pinfunction "1_1") (pintype "unspecified"))
      (node (ref "L5") (pin "2") (pinfunction "2_2") (pintype "unspecified"))
      (node (ref "R12") (pin "2") (pinfunction "2_2") (pintype "input"))
      (node (ref "R2") (pin "2") (pinfunction "2_2") (pintype "input"))
      (node (ref "R3") (pin "2") (pinfunction "2_2") (pintype "input"))
      (node (ref "R4") (pin "2") (pinfunction "2_2") (pintype "input"))
      (node (ref "R5") (pin "2") (pinfunction "2_2") (pintype "input"))
      (node (ref "U1") (pin "20") (pinfunction "VDD3P3_RTC_20") (pintype "unspecified"))
      (node (ref "U1") (pin "46") (pinfunction "VDD3P3_CPU_46") (pintype "unspecified"))
      (node (ref "U1") (pin "55") (pinfunction "VDDA_55") (pintype "unspecified"))
      (node (ref "U1") (pin "56") (pinfunction "VDDA_56") (pintype "unspecified"))
      (node (ref "U11") (pin "8") (pinfunction "VCC_8") (pintype "unspecified"))
      (node (ref "U2") (pin "3") (pinfunction "VIN_3") (pintype "unspecified"))
      (node (ref "U3") (pin "3") (pinfunction "VIN_3") (pintype "unspecified"))
      (node (ref "U5") (pin "6") (pinfunction "VIN_6") (pintype "unspecified"))
    )
    (net (code "46") (name "5V") (class "Default")
      (node (ref "H2") (pin "1") (pinfunction "1_1") (pintype "unspecified"))
      (node (ref "USB1") (pin "11") (pinfunction "VBUS_11") (pintype "unspecified"))
      (node (ref "USB1") (pin "2") (pinfunction "VBUS_2") (pintype "unspecified"))
    )
    (net (code "47") (name "24V") (class "Default")
      (node (ref "CN1") (pin "1") (pinfunction "1_1") (pintype "unspecified"))
      (node (ref "H2") (pin "3") (pinfunction "3_3") (pintype "unspecified"))
    )
    (net (code "48") (name "24V_5V") (class "Default")
      (node (ref "C28") (pin "1") (pinfunction "1_1") (pintype "unspecified"))
      (node (ref "C29") (pin "2") (pinfunction "2_2") (pintype "unspecified"))
      (node (ref "H2") (pin "2") (pinfunction "2_2") (pintype "unspecified"))
      (node (ref "R13") (pin "2") (pinfunction "2_2") (pintype "unspecified"))
      (node (ref "U9") (pin "5") (pinfunction "VIN_5") (pintype "unspecified"))
    )
    (net (code "49") (name "GND") (class "Default")
      (node (ref "C10") (pin "1") (pinfunction "1_1") (pintype "unspecified"))
      (node (ref "C11") (pin "1") (pinfunction "1_1") (pintype "input"))
      (node (ref "C12") (pin "1") (pinfunction "1_1") (pintype "unspecified"))
      (node (ref "C13") (pin "1") (pinfunction "1_1") (pintype "unspecified"))
      (node (ref "C14") (pin "1") (pinfunction "1_1") (pintype "unspecified"))
      (node (ref "C15") (pin "1") (pinfunction "1_1") (pintype "unspecified"))
      (node (ref "C16") (pin "1") (pinfunction "1_1") (pintype "unspecified"))
      (node (ref "C17") (pin "1") (pinfunction "1_1") (pintype "unspecified"))
      (node (ref "C18") (pin "1") (pinfunction "1_1") (pintype "unspecified"))
      (node (ref "C20") (pin "1") (pinfunction "1_1") (pintype "unspecified"))
      (node (ref "C21") (pin "1") (pinfunction "1_1") (pintype "unspecified"))
      (node (ref "C24") (pin "1") (pinfunction "1_1") (pintype "unspecified"))
      (node (ref "C25") (pin "1") (pinfunction "1_1") (pintype "unspecified"))
      (node (ref "C26") (pin "1") (pinfunction "1_1") (pintype "unspecified"))
      (node (ref "C27") (pin "1") (pinfunction "1_1") (pintype "unspecified"))
      (node (ref "C28") (pin "2") (pinfunction "2_2") (pintype "unspecified"))
      (node (ref "C29") (pin "1") (pinfunction "1_1") (pintype "unspecified"))
      (node (ref "C3") (pin "1") (pinfunction "1_1") (pintype "input"))
      (node (ref "C31") (pin "2") (pinfunction "2_2") (pintype "unspecified"))
      (node (ref "C32") (pin "1") (pinfunction "1_1") (pintype "unspecified"))
      (node (ref "C33") (pin "1") (pinfunction "1_1") (pintype "unspecified"))
      (node (ref "C34") (pin "1") (pinfunction "1_1") (pintype "unspecified"))
      (node (ref "C4") (pin "1") (pinfunction "1_1") (pintype "unspecified"))
      (node (ref "C5") (pin "2") (pinfunction "2_2") (pintype "input"))
      (node (ref "C6") (pin "1") (pinfunction "1_1") (pintype "unspecified"))
      (node (ref "C7") (pin "1") (pinfunction "1_1") (pintype "unspecified"))
      (node (ref "C8") (pin "1") (pinfunction "1_1") (pintype "unspecified"))
      (node (ref "C9") (pin "1") (pinfunction "1_1") (pintype "unspecified"))
      (node (ref "CN1") (pin "2") (pinfunction "2_2") (pintype "unspecified"))
      (node (ref "FPC1") (pin "15") (pinfunction "15_15") (pintype "unspecified"))
      (node (ref "FPC1") (pin "2") (pinfunction "2_2") (pintype "unspecified"))
      (node (ref "FPC1") (pin "25") (pinfunction "25_25") (pintype "unspecified"))
      (node (ref "FPC1") (pin "26") (pinfunction "26_26") (pintype "unspecified"))
      (node (ref "H3") (pin "5") (pinfunction "5_5") (pintype "unspecified"))
      (node (ref "L6") (pin "1") (pinfunction "1_1") (pintype "unspecified"))
      (node (ref "LED1") (pin "2") (pinfunction "-_2") (pintype "unspecified"))
      (node (ref "R10") (pin "1") (pinfunction "1_1") (pintype "input"))
      (node (ref "R14") (pin "1") (pinfunction "1_1") (pintype "unspecified"))
      (node (ref "R15") (pin "1") (pinfunction "1_1") (pintype "input"))
      (node (ref "R16") (pin "1") (pinfunction "1_1") (pintype "input"))
      (node (ref "R7") (pin "1") (pinfunction "1_1") (pintype "input"))
      (node (ref "SW1") (pin "2") (pinfunction "2_2") (pintype "unspecified"))
      (node (ref "SW1") (pin "3") (pinfunction "3_3") (pintype "unspecified"))
      (node (ref "SW1") (pin "4") (pinfunction "4_4") (pintype "unspecified"))
      (node (ref "SW2") (pin "2") (pinfunction "2_2") (pintype "unspecified"))
      (node (ref "SW2") (pin "3") (pinfunction "3_3") (pintype "unspecified"))
      (node (ref "SW2") (pin "4") (pinfunction "4_4") (pintype "unspecified"))
      (node (ref "SW3") (pin "2") (pinfunction "2_2") (pintype "unspecified"))
      (node (ref "SW3") (pin "3") (pinfunction "3_3") (pintype "unspecified"))
      (node (ref "SW3") (pin "4") (pinfunction "4_4") (pintype "unspecified"))
      (node (ref "U1") (pin "57") (pinfunction "GND_57") (pintype "unspecified"))
      (node (ref "U11") (pin "5") (pinfunction "GND_5") (pintype "unspecified"))
      (node (ref "U2") (pin "1") (pinfunction "VSS_1") (pintype "unspecified"))
      (node (ref "U3") (pin "1") (pinfunction "VSS_1") (pintype "unspecified"))
      (node (ref "U4") (pin "4") (pinfunction "GND_4") (pintype "unspecified"))
      (node (ref "U5") (pin "2") (pinfunction "GND_2") (pintype "unspecified"))
      (node (ref "U9") (pin "2") (pinfunction "GND_2") (pintype "unspecified"))
      (node (ref "USB1") (pin "1") (pinfunction "GND_1") (pintype "unspecified"))
      (node (ref "USB1") (pin "12") (pinfunction "GND_12") (pintype "unspecified"))
      (node (ref "USB1") (pin "13") (pinfunction "SHELL_13") (pintype "unspecified"))
      (node (ref "USB1") (pin "14") (pinfunction "SHELL_14") (pintype "unspecified"))
      (node (ref "X1") (pin "2") (pinfunction "GND_2") (pintype "input"))
      (node (ref "X1") (pin "4") (pinfunction "GND_4") (pintype "input"))
    )
    (net (code "50") (name "Net-(ANT1-ANT)") (class "Default")
      (node (ref "ANT1") (pin "1") (pinfunction "ANT_1") (pintype "input"))
      (node (ref "R1") (pin "1") (pinfunction "1_1") (pintype "input"))
    )
    (net (code "51") (name "Net-(C5-Pad1)") (class "Default")
      (node (ref "C5") (pin "1") (pinfunction "1_1") (pintype "input"))
      (node (ref "L3") (pin "2") (pinfunction "2_2") (pintype "unspecified"))
      (node (ref "X1") (pin "1") (pinfunction "1_1") (pintype "input"))
    )
    (net (code "52") (name "Net-(D1-A)") (class "Default")
      (node (ref "D1") (pin "2") (pinfunction "A_2") (pintype "unspecified"))
      (node (ref "L4") (pin "2") (pinfunction "2_2") (pintype "unspecified"))
      (node (ref "U5") (pin "1") (pinfunction "SW_1") (pintype "unspecified"))
    )
    (net (code "53") (name "Net-(L6-Pad2)") (class "Default")
      (node (ref "L6") (pin "2") (pinfunction "2_2") (pintype "unspecified"))
      (node (ref "R1") (pin "2") (pinfunction "2_2") (pintype "input"))
      (node (ref "R18") (pin "1") (pinfunction "1_1") (pintype "input"))
    )
    (net (code "54") (name "Net-(LED1-+)") (class "Default")
      (node (ref "LED1") (pin "1") (pinfunction "+_1") (pintype "unspecified"))
      (node (ref "R11") (pin "1") (pinfunction "1_1") (pintype "input"))
    )
    (net (code "55") (name "Net-(U1-GPIO45)") (class "Default")
      (node (ref "R5") (pin "1") (pinfunction "1_1") (pintype "input"))
      (node (ref "U1") (pin "51") (pinfunction "GPIO45_51") (pintype "unspecified"))
    )
    (net (code "56") (name "Net-(U1-LNA_IN)") (class "Default")
      (node (ref "R18") (pin "2") (pinfunction "2_2") (pintype "input"))
      (node (ref "U1") (pin "1") (pinfunction "LNA_IN_1") (pintype "unspecified"))
    )
    (net (code "57") (name "Net-(U1-U0TXD)") (class "Default")
      (node (ref "R6") (pin "1") (pinfunction "1_1") (pintype "unspecified"))
      (node (ref "U1") (pin "49") (pinfunction "U0TXD_49") (pintype "unspecified"))
    )
    (net (code "58") (name "Net-(U1-XTAL_N)") (class "Default")
      (node (ref "C11") (pin "2") (pinfunction "2_2") (pintype "input"))
      (node (ref "U1") (pin "53") (pinfunction "XTAL_N_53") (pintype "unspecified"))
      (node (ref "X1") (pin "3") (pinfunction "3_3") (pintype "input"))
    )
    (net (code "59") (name "Net-(U1-XTAL_P)") (class "Default")
      (node (ref "L3") (pin "1") (pinfunction "1_1") (pintype "unspecified"))
      (node (ref "U1") (pin "54") (pinfunction "XTAL_P_54") (pintype "unspecified"))
    )
    (net (code "60") (name "Net-(U6-K)") (class "Default")
      (node (ref "U6") (pin "1") (pinfunction "K_1") (pintype "unspecified"))
      (node (ref "U7") (pin "2") (pinfunction "A_2") (pintype "unspecified"))
    )
    (net (code "61") (name "Net-(U7-K)") (class "Default")
      (node (ref "U7") (pin "1") (pinfunction "K_1") (pintype "unspecified"))
      (node (ref "U8") (pin "2") (pinfunction "A_2") (pintype "unspecified"))
    )
    (net (code "62") (name "Net-(U9-BOOT)") (class "Default")
      (node (ref "C22") (pin "2") (pinfunction "2_2") (pintype "unspecified"))
      (node (ref "U9") (pin "1") (pinfunction "BOOT_1") (pintype "unspecified"))
    )
    (net (code "63") (name "Net-(U9-EN)") (class "Default")
      (node (ref "R13") (pin "1") (pinfunction "1_1") (pintype "unspecified"))
      (node (ref "U9") (pin "4") (pinfunction "EN_4") (pintype "unspecified"))
    )
    (net (code "64") (name "Net-(U9-FB)") (class "Default")
      (node (ref "R12") (pin "1") (pinfunction "1_1") (pintype "input"))
      (node (ref "R14") (pin "2") (pinfunction "2_2") (pintype "unspecified"))
      (node (ref "U9") (pin "3") (pinfunction "FB_3") (pintype "unspecified"))
    )
    (net (code "65") (name "Net-(U9-SW)") (class "Default")
      (node (ref "C22") (pin "1") (pinfunction "1_1") (pintype "unspecified"))
      (node (ref "L5") (pin "1") (pinfunction "1_1") (pintype "unspecified"))
      (node (ref "U9") (pin "6") (pinfunction "SW_6") (pintype "unspecified"))
    )
    (net (code "66") (name "Net-(U10-A)") (class "Default")
      (node (ref "U10") (pin "2") (pinfunction "A_2") (pintype "unspecified"))
      (node (ref "U8") (pin "1") (pinfunction "K_1") (pintype "unspecified"))
    )
    (net (code "67") (name "Net-(USB1-CC1)") (class "Default")
      (node (ref "R10") (pin "2") (pinfunction "2_2") (pintype "input"))
      (node (ref "USB1") (pin "4") (pinfunction "CC1_4") (pintype "unspecified"))
    )
    (net (code "68") (name "Net-(USB1-CC2)") (class "Default")
      (node (ref "R7") (pin "2") (pinfunction "2_2") (pintype "input"))
      (node (ref "USB1") (pin "10") (pinfunction "CC2_10") (pintype "unspecified"))
    )
    (net (code "69") (name "VDD3P3") (class "Default")
      (node (ref "C9") (pin "2") (pinfunction "2_2") (pintype "unspecified"))
      (node (ref "L2") (pin "2") (pinfunction "2_2") (pintype "unspecified"))
      (node (ref "U1") (pin "2") (pinfunction "VDD3P3_2") (pintype "unspecified"))
      (node (ref "U1") (pin "3") (pinfunction "VDD3P3_3") (pintype "unspecified"))
    )
    (net (code "70") (name "VDD_SPI") (class "Default")
      (node (ref "C20") (pin "2") (pinfunction "2_2") (pintype "unspecified"))
      (node (ref "C21") (pin "2") (pinfunction "2_2") (pintype "unspecified"))
      (node (ref "U1") (pin "29") (pinfunction "VDD_SPI_29") (pintype "unspecified"))
      (node (ref "U4") (pin "8") (pinfunction "VCC_8") (pintype "unspecified"))
    )
    (net (code "71") (name "unconnected-(ANT1-NC-Pad2)") (class "Default")
      (node (ref "ANT1") (pin "2") (pinfunction "NC_2") (pintype "input+no_connect"))
    )
    (net (code "72") (name "unconnected-(FPC1-Pad1)") (class "Default")
      (node (ref "FPC1") (pin "1") (pinfunction "1_1") (pintype "unspecified+no_connect"))
    )
    (net (code "73") (name "unconnected-(FPC1-Pad23)") (class "Default")
      (node (ref "FPC1") (pin "23") (pinfunction "23_23") (pintype "unspecified+no_connect"))
    )
    (net (code "74") (name "unconnected-(FPC1-Pad24)") (class "Default")
      (node (ref "FPC1") (pin "24") (pinfunction "24_24") (pintype "unspecified+no_connect"))
    )
    (net (code "75") (name "unconnected-(U1-GPIO33-Pad38)") (class "Default")
      (node (ref "U1") (pin "38") (pinfunction "GPIO33_38") (pintype "unspecified+no_connect"))
    )
    (net (code "76") (name "unconnected-(U1-GPIO34-Pad39)") (class "Default")
      (node (ref "U1") (pin "39") (pinfunction "GPIO34_39") (pintype "unspecified+no_connect"))
    )
    (net (code "77") (name "unconnected-(U1-GPIO35-Pad40)") (class "Default")
      (node (ref "U1") (pin "40") (pinfunction "GPIO35_40") (pintype "unspecified+no_connect"))
    )
    (net (code "78") (name "unconnected-(U1-GPIO36-Pad41)") (class "Default")
      (node (ref "U1") (pin "41") (pinfunction "GPIO36_41") (pintype "unspecified+no_connect"))
    )
    (net (code "79") (name "unconnected-(U1-GPIO37-Pad42)") (class "Default")
      (node (ref "U1") (pin "42") (pinfunction "GPIO37_42") (pintype "unspecified+no_connect"))
    )
    (net (code "80") (name "unconnected-(U1-GPIO46-Pad52)") (class "Default")
      (node (ref "U1") (pin "52") (pinfunction "GPIO46_52") (pintype "unspecified+no_connect"))
    )
    (net (code "81") (name "unconnected-(U1-MTDI-Pad47)") (class "Default")
      (node (ref "U1") (pin "47") (pinfunction "MTDI_47") (pintype "unspecified+no_connect"))
    )
    (net (code "82") (name "unconnected-(U1-MTMS-Pad48)") (class "Default")
      (node (ref "U1") (pin "48") (pinfunction "MTMS_48") (pintype "unspecified+no_connect"))
    )
    (net (code "83") (name "unconnected-(U1-SPICS1-Pad28)") (class "Default")
      (node (ref "U1") (pin "28") (pinfunction "SPICS1_28") (pintype "unspecified+no_connect"))
    )
    (net (code "84") (name "unconnected-(USB1-SBU1-Pad9)") (class "Default")
      (node (ref "USB1") (pin "9") (pinfunction "SBU1_9") (pintype "unspecified+no_connect"))
    )
    (net (code "85") (name "unconnected-(USB1-SBU2-Pad3)") (class "Default")
      (node (ref "USB1") (pin "3") (pinfunction "SBU2_3") (pintype "unspecified+no_connect"))
    )
  )
)
